# rec_2dek.net
KiCad netlist of a schematic drawn in EAGLE
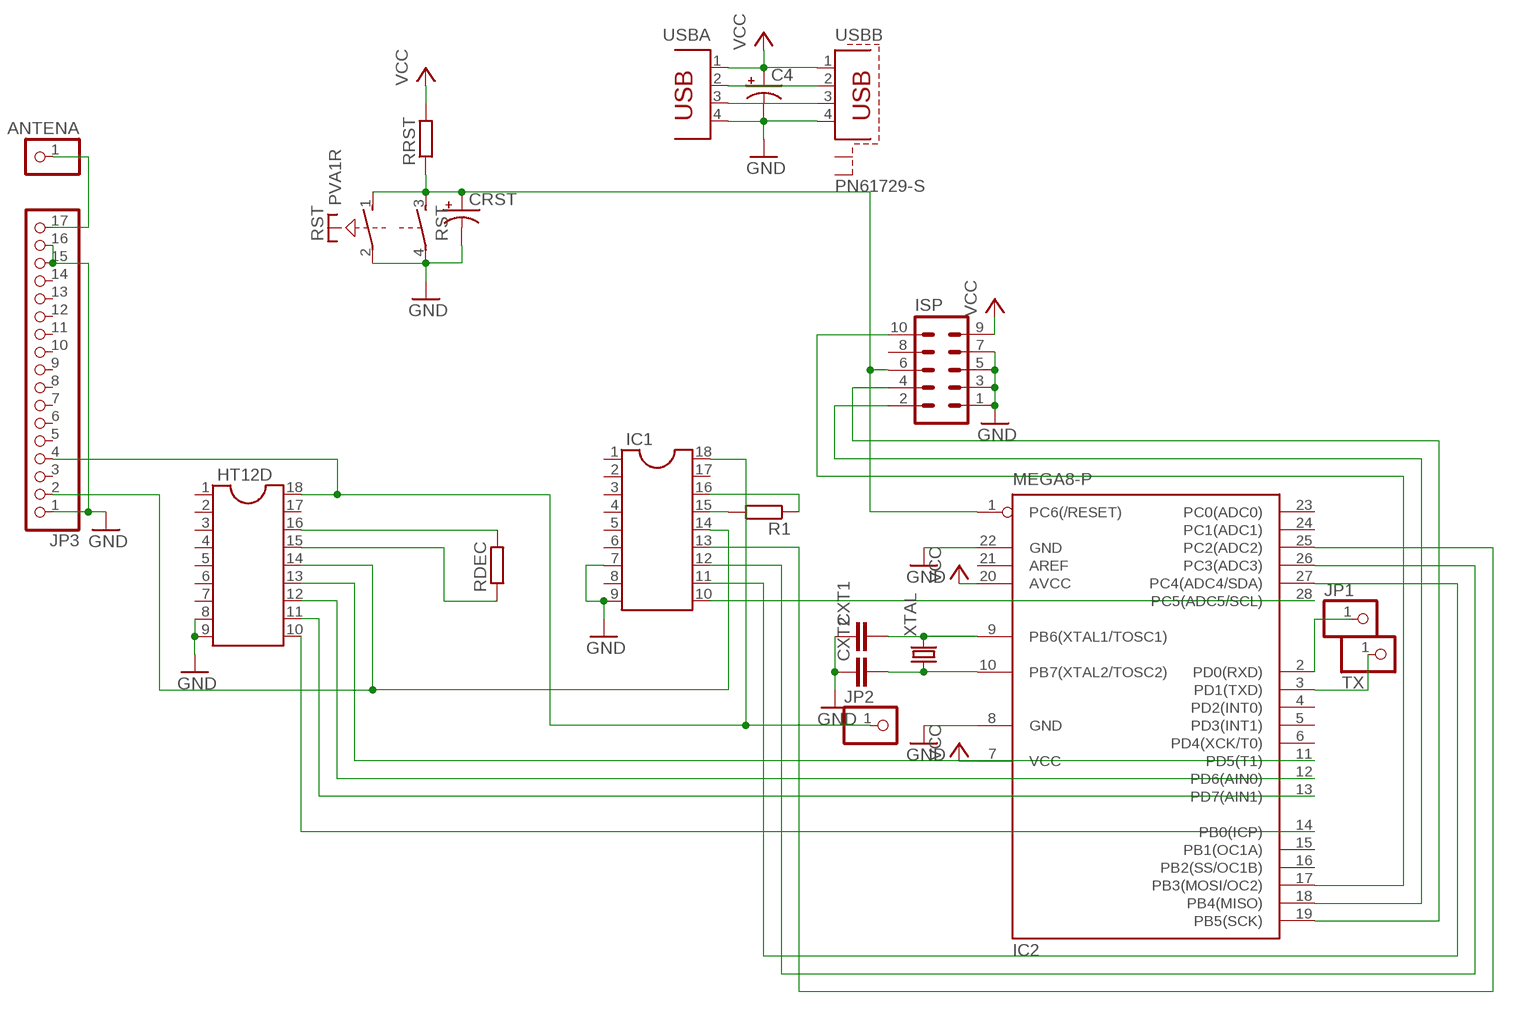
[diagram p0: schematic, sheet 1]

(export (version "E")
  (design (tool "Eeschema 10.0.6"))
  (components
    (comp (ref "ANTENA")
      (value "PINHD-1X1")
      (footprint "eagle-import:1X01")
      (libsource (lib "eagle-import") (part "PINHD-1X1"))
    )
    (comp (ref "C4")
      (value "CPOL-USE2.5-7")
      (footprint "eagle-import:E2,5-7")
      (libsource (lib "eagle-import") (part "CPOL-USE2.5-7"))
    )
    (comp (ref "CRST")
      (value "CPOL-USE2.5-7")
      (footprint "eagle-import:E2,5-7")
      (libsource (lib "eagle-import") (part "CPOL-USE2.5-7"))
    )
    (comp (ref "CXT1")
      (value "C2.5/2")
      (footprint "eagle-import:C2.5-2")
      (libsource (lib "eagle-import") (part "C2.5/2"))
    )
    (comp (ref "CXT2")
      (value "C2.5/2")
      (footprint "eagle-import:C2.5-2")
      (libsource (lib "eagle-import") (part "C2.5/2"))
    )
    (comp (ref "HT12D")
      (value "DIL18S")
      (footprint "eagle-import:SOCKET-18")
      (libsource (lib "eagle-import") (part "DIL18S"))
    )
    (comp (ref "IC1")
      (value "DIL18S")
      (footprint "eagle-import:SOCKET-18")
      (libsource (lib "eagle-import") (part "DIL18S"))
    )
    (comp (ref "IC2")
      (value "MEGA8-P")
      (footprint "eagle-import:DIL28-3")
      (libsource (lib "eagle-import") (part "MEGA8-P"))
    )
    (comp (ref "ISP")
      (value "MA05-2")
      (footprint "eagle-import:MA05-2")
      (libsource (lib "eagle-import") (part "MA05-2"))
    )
    (comp (ref "JP1")
      (value "PINHD-1X1")
      (footprint "eagle-import:1X01")
      (libsource (lib "eagle-import") (part "PINHD-1X1"))
    )
    (comp (ref "JP2")
      (value "PINHD-1X1")
      (footprint "eagle-import:1X01")
      (libsource (lib "eagle-import") (part "PINHD-1X1"))
    )
    (comp (ref "JP3")
      (value "PINHD-1X17")
      (footprint "eagle-import:1X17")
      (libsource (lib "eagle-import") (part "PINHD-1X17"))
    )
    (comp (ref "R1")
      (value "R-EU_0207/12")
      (footprint "eagle-import:0207_12")
      (libsource (lib "eagle-import") (part "R-EU_0207/12"))
    )
    (comp (ref "RDEC")
      (value "R-EU_0309/12")
      (footprint "eagle-import:0309_12")
      (libsource (lib "eagle-import") (part "R-EU_0309/12"))
    )
    (comp (ref "RRST")
      (value "R-EU_0207/10")
      (footprint "eagle-import:0207_10")
      (libsource (lib "eagle-import") (part "R-EU_0207/10"))
    )
    (comp (ref "RST")
      (value "PVA1R")
      (footprint "eagle-import:PVA1R")
      (libsource (lib "eagle-import") (part "PVA1R"))
    )
    (comp (ref "TX")
      (value "PINHD-1X1")
      (footprint "eagle-import:1X01")
      (libsource (lib "eagle-import") (part "PINHD-1X1"))
    )
    (comp (ref "USBA")
      (value "PN87520")
      (footprint "eagle-import:PN87520")
      (libsource (lib "eagle-import") (part "PN87520"))
    )
    (comp (ref "USBB")
      (value "PN61729-S")
      (footprint "eagle-import:PN61729-S")
      (libsource (lib "eagle-import") (part "PN61729-S"))
    )
    (comp (ref "XTAL")
      (value "CRYSTALHC49S")
      (footprint "eagle-import:HC49_S")
      (libsource (lib "eagle-import") (part "CRYSTALHC49S"))
    )
  )
  (nets
    (net (code "1") (name "GND") (class "Default")
      (node (ref "C4") (pin "-") (pinfunction "-_-") (pintype "passive"))
      (node (ref "CRST") (pin "-") (pinfunction "-_-") (pintype "passive"))
      (node (ref "CXT1") (pin "1") (pinfunction "1_1") (pintype "passive"))
      (node (ref "CXT2") (pin "1") (pinfunction "1_1") (pintype "passive"))
      (node (ref "HT12D") (pin "8") (pinfunction "8_8") (pintype "passive"))
      (node (ref "HT12D") (pin "9") (pinfunction "9_9") (pintype "passive"))
      (node (ref "IC1") (pin "7") (pinfunction "7_7") (pintype "passive"))
      (node (ref "IC1") (pin "9") (pinfunction "9_9") (pintype "passive"))
      (node (ref "IC2") (pin "22") (pinfunction "GND_22") (pintype "power_in"))
      (node (ref "IC2") (pin "8") (pinfunction "GND_8") (pintype "power_in"))
      (node (ref "ISP") (pin "1") (pinfunction "1_1") (pintype "passive"))
      (node (ref "ISP") (pin "3") (pinfunction "3_3") (pintype "passive"))
      (node (ref "ISP") (pin "5") (pinfunction "5_5") (pintype "passive"))
      (node (ref "ISP") (pin "7") (pinfunction "7_7") (pintype "passive"))
      (node (ref "JP3") (pin "1") (pinfunction "1_1") (pintype "passive"))
      (node (ref "JP3") (pin "15") (pinfunction "15_15") (pintype "passive"))
      (node (ref "JP3") (pin "16") (pinfunction "16_16") (pintype "passive"))
      (node (ref "RST") (pin "2") (pinfunction "P_2") (pintype "passive"))
      (node (ref "RST") (pin "4") (pinfunction "P_4") (pintype "passive"))
      (node (ref "USBA") (pin "4") (pinfunction "4_4") (pintype "passive"))
      (node (ref "USBB") (pin "4") (pinfunction "4_4") (pintype "passive"))
    )
    (net (code "2") (name "Net-(ANTENA-Pad1)") (class "Default")
      (node (ref "ANTENA") (pin "1") (pinfunction "1_1") (pintype "passive"))
      (node (ref "JP3") (pin "17") (pinfunction "17_17") (pintype "passive"))
    )
    (net (code "3") (name "Net-(HT12D-Pad14)") (class "Default")
      (node (ref "HT12D") (pin "14") (pinfunction "14_14") (pintype "passive"))
      (node (ref "IC1") (pin "14") (pinfunction "14_14") (pintype "passive"))
      (node (ref "JP3") (pin "2") (pinfunction "2_2") (pintype "passive"))
    )
    (net (code "4") (name "Net-(HT12D-Pad15)") (class "Default")
      (node (ref "HT12D") (pin "15") (pinfunction "15_15") (pintype "passive"))
      (node (ref "RDEC") (pin "1") (pinfunction "1_1") (pintype "passive"))
    )
    (net (code "5") (name "Net-(HT12D-Pad16)") (class "Default")
      (node (ref "HT12D") (pin "16") (pinfunction "16_16") (pintype "passive"))
      (node (ref "RDEC") (pin "2") (pinfunction "2_2") (pintype "passive"))
    )
    (net (code "6") (name "Net-(HT12D-Pad18)") (class "Default")
      (node (ref "HT12D") (pin "18") (pinfunction "18_18") (pintype "passive"))
      (node (ref "IC1") (pin "18") (pinfunction "18_18") (pintype "passive"))
      (node (ref "JP2") (pin "1") (pinfunction "1_1") (pintype "passive"))
      (node (ref "JP3") (pin "4") (pinfunction "4_4") (pintype "passive"))
    )
    (net (code "7") (name "Net-(IC1-Pad15)") (class "Default")
      (node (ref "IC1") (pin "15") (pinfunction "15_15") (pintype "passive"))
      (node (ref "R1") (pin "2") (pinfunction "2_2") (pintype "passive"))
    )
    (net (code "8") (name "Net-(IC1-Pad16)") (class "Default")
      (node (ref "IC1") (pin "16") (pinfunction "16_16") (pintype "passive"))
      (node (ref "R1") (pin "1") (pinfunction "1_1") (pintype "passive"))
    )
    (net (code "9") (name "Net-(IC2-PB0(ICP))") (class "Default")
      (node (ref "HT12D") (pin "10") (pinfunction "10_10") (pintype "passive"))
      (node (ref "IC2") (pin "14") (pinfunction "PB0(ICP)_14") (pintype "bidirectional"))
    )
    (net (code "10") (name "Net-(IC2-PB3(MOSI{slash}OC2))") (class "Default")
      (node (ref "IC2") (pin "17") (pinfunction "PB3(MOSI/OC2)_17") (pintype "bidirectional"))
      (node (ref "ISP") (pin "10") (pinfunction "10_10") (pintype "passive"))
    )
    (net (code "11") (name "Net-(IC2-PB4(MISO))") (class "Default")
      (node (ref "IC2") (pin "18") (pinfunction "PB4(MISO)_18") (pintype "bidirectional"))
      (node (ref "ISP") (pin "2") (pinfunction "2_2") (pintype "passive"))
    )
    (net (code "12") (name "Net-(IC2-PB5(SCK))") (class "Default")
      (node (ref "IC2") (pin "19") (pinfunction "PB5(SCK)_19") (pintype "bidirectional"))
      (node (ref "ISP") (pin "4") (pinfunction "4_4") (pintype "passive"))
    )
    (net (code "13") (name "Net-(IC2-PB6(XTAL1{slash}TOSC1))") (class "Default")
      (node (ref "CXT1") (pin "2") (pinfunction "2_2") (pintype "passive"))
      (node (ref "IC2") (pin "9") (pinfunction "PB6(XTAL1/TOSC1)_9") (pintype "bidirectional"))
      (node (ref "XTAL") (pin "2") (pinfunction "2_2") (pintype "passive"))
    )
    (net (code "14") (name "Net-(IC2-PB7(XTAL2{slash}TOSC2))") (class "Default")
      (node (ref "CXT2") (pin "2") (pinfunction "2_2") (pintype "passive"))
      (node (ref "IC2") (pin "10") (pinfunction "PB7(XTAL2/TOSC2)_10") (pintype "bidirectional"))
      (node (ref "XTAL") (pin "1") (pinfunction "1_1") (pintype "passive"))
    )
    (net (code "15") (name "Net-(IC2-PC2(ADC2))") (class "Default")
      (node (ref "IC1") (pin "13") (pinfunction "13_13") (pintype "passive"))
      (node (ref "IC2") (pin "25") (pinfunction "PC2(ADC2)_25") (pintype "bidirectional"))
    )
    (net (code "16") (name "Net-(IC2-PC3(ADC3))") (class "Default")
      (node (ref "IC1") (pin "12") (pinfunction "12_12") (pintype "passive"))
      (node (ref "IC2") (pin "26") (pinfunction "PC3(ADC3)_26") (pintype "bidirectional"))
    )
    (net (code "17") (name "Net-(IC2-PC4(ADC4{slash}SDA))") (class "Default")
      (node (ref "IC1") (pin "11") (pinfunction "11_11") (pintype "passive"))
      (node (ref "IC2") (pin "27") (pinfunction "PC4(ADC4/SDA)_27") (pintype "bidirectional"))
    )
    (net (code "18") (name "Net-(IC2-PC5(ADC5{slash}SCL))") (class "Default")
      (node (ref "IC1") (pin "10") (pinfunction "10_10") (pintype "passive"))
      (node (ref "IC2") (pin "28") (pinfunction "PC5(ADC5/SCL)_28") (pintype "bidirectional"))
    )
    (net (code "19") (name "Net-(IC2-PC6({slash}RESET))") (class "Default")
      (node (ref "CRST") (pin "+") (pinfunction "+_+") (pintype "passive"))
      (node (ref "IC2") (pin "1") (pinfunction "PC6(/RESET)_1") (pintype "bidirectional"))
      (node (ref "ISP") (pin "6") (pinfunction "6_6") (pintype "passive"))
      (node (ref "RRST") (pin "1") (pinfunction "1_1") (pintype "passive"))
      (node (ref "RST") (pin "1") (pinfunction "S_1") (pintype "passive"))
      (node (ref "RST") (pin "3") (pinfunction "S_3") (pintype "passive"))
    )
    (net (code "20") (name "Net-(IC2-PD0(RXD))") (class "Default")
      (node (ref "IC2") (pin "2") (pinfunction "PD0(RXD)_2") (pintype "bidirectional"))
      (node (ref "JP1") (pin "1") (pinfunction "1_1") (pintype "passive"))
    )
    (net (code "21") (name "Net-(IC2-PD1(TXD))") (class "Default")
      (node (ref "IC2") (pin "3") (pinfunction "PD1(TXD)_3") (pintype "bidirectional"))
      (node (ref "TX") (pin "1") (pinfunction "1_1") (pintype "passive"))
    )
    (net (code "22") (name "Net-(IC2-PD5(T1))") (class "Default")
      (node (ref "HT12D") (pin "13") (pinfunction "13_13") (pintype "passive"))
      (node (ref "IC2") (pin "11") (pinfunction "PD5(T1)_11") (pintype "bidirectional"))
    )
    (net (code "23") (name "Net-(IC2-PD6(AIN0))") (class "Default")
      (node (ref "HT12D") (pin "12") (pinfunction "12_12") (pintype "passive"))
      (node (ref "IC2") (pin "12") (pinfunction "PD6(AIN0)_12") (pintype "bidirectional"))
    )
    (net (code "24") (name "Net-(IC2-PD7(AIN1))") (class "Default")
      (node (ref "HT12D") (pin "11") (pinfunction "11_11") (pintype "passive"))
      (node (ref "IC2") (pin "13") (pinfunction "PD7(AIN1)_13") (pintype "bidirectional"))
    )
    (net (code "25") (name "Net-(USBA-Pad2)") (class "Default")
      (node (ref "USBA") (pin "2") (pinfunction "2_2") (pintype "passive"))
      (node (ref "USBB") (pin "2") (pinfunction "2_2") (pintype "passive"))
    )
    (net (code "26") (name "Net-(USBA-Pad3)") (class "Default")
      (node (ref "USBA") (pin "3") (pinfunction "3_3") (pintype "passive"))
      (node (ref "USBB") (pin "3") (pinfunction "3_3") (pintype "passive"))
    )
    (net (code "27") (name "VCC") (class "Default")
      (node (ref "C4") (pin "+") (pinfunction "+_+") (pintype "passive"))
      (node (ref "IC2") (pin "20") (pinfunction "AVCC_20") (pintype "power_in"))
      (node (ref "IC2") (pin "7") (pinfunction "VCC_7") (pintype "power_in"))
      (node (ref "ISP") (pin "9") (pinfunction "9_9") (pintype "passive"))
      (node (ref "RRST") (pin "2") (pinfunction "2_2") (pintype "passive"))
      (node (ref "USBA") (pin "1") (pinfunction "1_1") (pintype "passive"))
      (node (ref "USBB") (pin "1") (pinfunction "1_1") (pintype "passive"))
    )
    (net (code "28") (name "unconnected-(HT12D-Pad1)") (class "Default")
      (node (ref "HT12D") (pin "1") (pinfunction "1_1") (pintype "passive"))
    )
    (net (code "29") (name "unconnected-(HT12D-Pad2)") (class "Default")
      (node (ref "HT12D") (pin "2") (pinfunction "2_2") (pintype "passive"))
    )
    (net (code "30") (name "unconnected-(HT12D-Pad3)") (class "Default")
      (node (ref "HT12D") (pin "3") (pinfunction "3_3") (pintype "passive"))
    )
    (net (code "31") (name "unconnected-(HT12D-Pad4)") (class "Default")
      (node (ref "HT12D") (pin "4") (pinfunction "4_4") (pintype "passive"))
    )
    (net (code "32") (name "unconnected-(HT12D-Pad5)") (class "Default")
      (node (ref "HT12D") (pin "5") (pinfunction "5_5") (pintype "passive"))
    )
    (net (code "33") (name "unconnected-(HT12D-Pad6)") (class "Default")
      (node (ref "HT12D") (pin "6") (pinfunction "6_6") (pintype "passive"))
    )
    (net (code "34") (name "unconnected-(HT12D-Pad7)") (class "Default")
      (node (ref "HT12D") (pin "7") (pinfunction "7_7") (pintype "passive"))
    )
    (net (code "35") (name "unconnected-(HT12D-Pad17)") (class "Default")
      (node (ref "HT12D") (pin "17") (pinfunction "17_17") (pintype "passive"))
    )
    (net (code "36") (name "unconnected-(IC1-Pad1)") (class "Default")
      (node (ref "IC1") (pin "1") (pinfunction "1_1") (pintype "passive"))
    )
    (net (code "37") (name "unconnected-(IC1-Pad2)") (class "Default")
      (node (ref "IC1") (pin "2") (pinfunction "2_2") (pintype "passive"))
    )
    (net (code "38") (name "unconnected-(IC1-Pad3)") (class "Default")
      (node (ref "IC1") (pin "3") (pinfunction "3_3") (pintype "passive"))
    )
    (net (code "39") (name "unconnected-(IC1-Pad4)") (class "Default")
      (node (ref "IC1") (pin "4") (pinfunction "4_4") (pintype "passive"))
    )
    (net (code "40") (name "unconnected-(IC1-Pad5)") (class "Default")
      (node (ref "IC1") (pin "5") (pinfunction "5_5") (pintype "passive"))
    )
    (net (code "41") (name "unconnected-(IC1-Pad6)") (class "Default")
      (node (ref "IC1") (pin "6") (pinfunction "6_6") (pintype "passive"))
    )
    (net (code "42") (name "unconnected-(IC1-Pad8)") (class "Default")
      (node (ref "IC1") (pin "8") (pinfunction "8_8") (pintype "passive"))
    )
    (net (code "43") (name "unconnected-(IC1-Pad17)") (class "Default")
      (node (ref "IC1") (pin "17") (pinfunction "17_17") (pintype "passive"))
    )
    (net (code "44") (name "unconnected-(IC2-AREF-Pad21)") (class "Default")
      (node (ref "IC2") (pin "21") (pinfunction "AREF_21") (pintype "passive"))
    )
    (net (code "45") (name "unconnected-(IC2-PB1(OC1A)-Pad15)") (class "Default")
      (node (ref "IC2") (pin "15") (pinfunction "PB1(OC1A)_15") (pintype "bidirectional"))
    )
    (net (code "46") (name "unconnected-(IC2-PB2(SS{slash}OC1B)-Pad16)") (class "Default")
      (node (ref "IC2") (pin "16") (pinfunction "PB2(SS/OC1B)_16") (pintype "bidirectional"))
    )
    (net (code "47") (name "unconnected-(IC2-PC0(ADC0)-Pad23)") (class "Default")
      (node (ref "IC2") (pin "23") (pinfunction "PC0(ADC0)_23") (pintype "bidirectional"))
    )
    (net (code "48") (name "unconnected-(IC2-PC1(ADC1)-Pad24)") (class "Default")
      (node (ref "IC2") (pin "24") (pinfunction "PC1(ADC1)_24") (pintype "bidirectional"))
    )
    (net (code "49") (name "unconnected-(IC2-PD2(INT0)-Pad4)") (class "Default")
      (node (ref "IC2") (pin "4") (pinfunction "PD2(INT0)_4") (pintype "bidirectional"))
    )
    (net (code "50") (name "unconnected-(IC2-PD3(INT1)-Pad5)") (class "Default")
      (node (ref "IC2") (pin "5") (pinfunction "PD3(INT1)_5") (pintype "bidirectional"))
    )
    (net (code "51") (name "unconnected-(IC2-PD4(XCK{slash}T0)-Pad6)") (class "Default")
      (node (ref "IC2") (pin "6") (pinfunction "PD4(XCK/T0)_6") (pintype "bidirectional"))
    )
    (net (code "52") (name "unconnected-(ISP-Pad8)") (class "Default")
      (node (ref "ISP") (pin "8") (pinfunction "8_8") (pintype "passive"))
    )
    (net (code "53") (name "unconnected-(JP3-Pad3)") (class "Default")
      (node (ref "JP3") (pin "3") (pinfunction "3_3") (pintype "passive"))
    )
    (net (code "54") (name "unconnected-(JP3-Pad5)") (class "Default")
      (node (ref "JP3") (pin "5") (pinfunction "5_5") (pintype "passive"))
    )
    (net (code "55") (name "unconnected-(JP3-Pad6)") (class "Default")
      (node (ref "JP3") (pin "6") (pinfunction "6_6") (pintype "passive"))
    )
    (net (code "56") (name "unconnected-(JP3-Pad7)") (class "Default")
      (node (ref "JP3") (pin "7") (pinfunction "7_7") (pintype "passive"))
    )
    (net (code "57") (name "unconnected-(JP3-Pad8)") (class "Default")
      (node (ref "JP3") (pin "8") (pinfunction "8_8") (pintype "passive"))
    )
    (net (code "58") (name "unconnected-(JP3-Pad9)") (class "Default")
      (node (ref "JP3") (pin "9") (pinfunction "9_9") (pintype "passive"))
    )
    (net (code "59") (name "unconnected-(JP3-Pad10)") (class "Default")
      (node (ref "JP3") (pin "10") (pinfunction "10_10") (pintype "passive"))
    )
    (net (code "60") (name "unconnected-(JP3-Pad11)") (class "Default")
      (node (ref "JP3") (pin "11") (pinfunction "11_11") (pintype "passive"))
    )
    (net (code "61") (name "unconnected-(JP3-Pad12)") (class "Default")
      (node (ref "JP3") (pin "12") (pinfunction "12_12") (pintype "passive"))
    )
    (net (code "62") (name "unconnected-(JP3-Pad13)") (class "Default")
      (node (ref "JP3") (pin "13") (pinfunction "13_13") (pintype "passive"))
    )
    (net (code "63") (name "unconnected-(JP3-Pad14)") (class "Default")
      (node (ref "JP3") (pin "14") (pinfunction "14_14") (pintype "passive"))
    )
    (net (code "64") (name "unconnected-(USBB-PadS1)") (class "Default")
      (node (ref "USBB") (pin "S1") (pinfunction "S1_S1") (pintype "passive"))
    )
    (net (code "65") (name "unconnected-(USBB-PadS2)") (class "Default")
      (node (ref "USBB") (pin "S2") (pinfunction "S2_S2") (pintype "passive"))
    )
  )
)
